# MOD.net
KiCad netlist of a schematic drawn in EAGLE
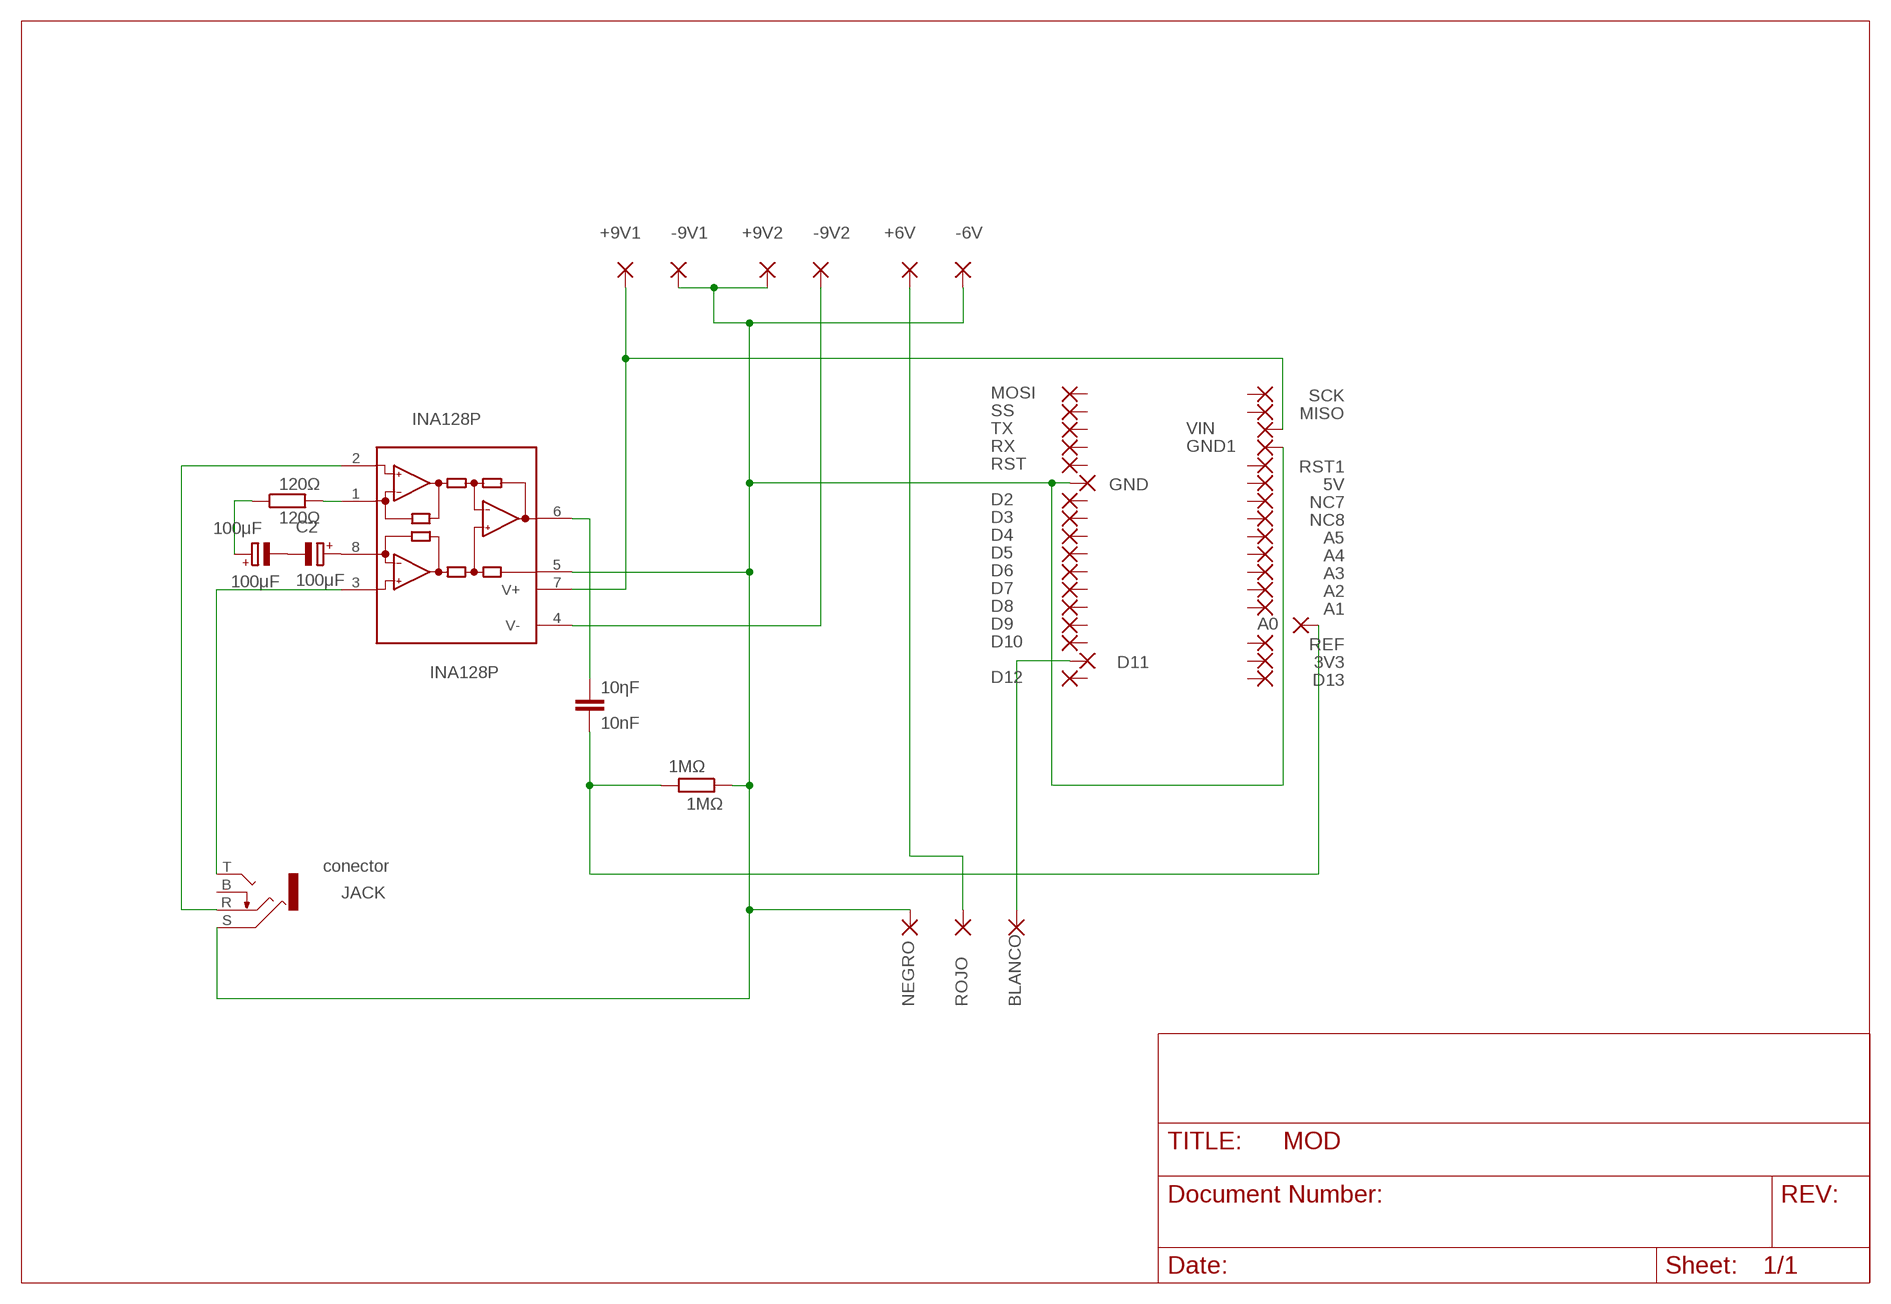
[diagram p0: schematic, sheet 1]

(export (version "E")
  (design (tool "Eeschema 10.0.6"))
  (components
    (comp (ref "+6V")
      (value "2,54/1,1")
      (footprint "eagle-import:2,54_1,1")
      (libsource (lib "eagle-import") (part "2,54/1,1"))
    )
    (comp (ref "+9V1")
      (value "2,54/1,1")
      (footprint "eagle-import:2,54_1,1")
      (libsource (lib "eagle-import") (part "2,54/1,1"))
    )
    (comp (ref "+9V2")
      (value "2,54/1,1")
      (footprint "eagle-import:2,54_1,1")
      (libsource (lib "eagle-import") (part "2,54/1,1"))
    )
    (comp (ref "-6V")
      (value "2,54/1,1")
      (footprint "eagle-import:2,54_1,1")
      (libsource (lib "eagle-import") (part "2,54/1,1"))
    )
    (comp (ref "-9V1")
      (value "2,54/1,1")
      (footprint "eagle-import:2,54_1,1")
      (libsource (lib "eagle-import") (part "2,54/1,1"))
    )
    (comp (ref "-9V2")
      (value "2,54/1,1")
      (footprint "eagle-import:2,54_1,1")
      (libsource (lib "eagle-import") (part "2,54/1,1"))
    )
    (comp (ref "1MΩ")
      (value "1MΩ")
      (footprint "eagle-import:0207_15")
      (libsource (lib "eagle-import") (part "R-EU_0207/15"))
    )
    (comp (ref "3V3")
      (value "1,6/0,9")
      (footprint "eagle-import:1,6_0,9")
      (libsource (lib "eagle-import") (part "1,6/0,9"))
    )
    (comp (ref "5V")
      (value "1,6/0,9")
      (footprint "eagle-import:1,6_0,9")
      (libsource (lib "eagle-import") (part "1,6/0,9"))
    )
    (comp (ref "10ηF")
      (value "10nF")
      (footprint "eagle-import:C050-030X075")
      (libsource (lib "eagle-import") (part "C-EU050-030X075"))
    )
    (comp (ref "100μF")
      (value "100μF")
      (footprint "eagle-import:B45181B")
      (libsource (lib "eagle-import") (part "CPOL-EUB45181B"))
    )
    (comp (ref "120Ω")
      (value "120Ω")
      (footprint "eagle-import:0207_15")
      (libsource (lib "eagle-import") (part "R-EU_0207/15"))
    )
    (comp (ref "A0")
      (value "1,6/0,9")
      (footprint "eagle-import:1,6_0,9")
      (libsource (lib "eagle-import") (part "1,6/0,9"))
    )
    (comp (ref "A1")
      (value "1,6/0,9")
      (footprint "eagle-import:1,6_0,9")
      (libsource (lib "eagle-import") (part "1,6/0,9"))
    )
    (comp (ref "A2")
      (value "1,6/0,9")
      (footprint "eagle-import:1,6_0,9")
      (libsource (lib "eagle-import") (part "1,6/0,9"))
    )
    (comp (ref "A3")
      (value "1,6/0,9")
      (footprint "eagle-import:1,6_0,9")
      (libsource (lib "eagle-import") (part "1,6/0,9"))
    )
    (comp (ref "A4")
      (value "1,6/0,9")
      (footprint "eagle-import:1,6_0,9")
      (libsource (lib "eagle-import") (part "1,6/0,9"))
    )
    (comp (ref "A5")
      (value "1,6/0,9")
      (footprint "eagle-import:1,6_0,9")
      (libsource (lib "eagle-import") (part "1,6/0,9"))
    )
    (comp (ref "BLANCO")
      (value "1,6/0,9")
      (footprint "eagle-import:1,6_0,9")
      (libsource (lib "eagle-import") (part "1,6/0,9"))
    )
    (comp (ref "C2")
      (value "100μF")
      (footprint "eagle-import:B45181B")
      (libsource (lib "eagle-import") (part "CPOL-EUB45181B"))
    )
    (comp (ref "D2")
      (value "1,6/0,9")
      (footprint "eagle-import:1,6_0,9")
      (libsource (lib "eagle-import") (part "1,6/0,9"))
    )
    (comp (ref "D3")
      (value "1,6/0,9")
      (footprint "eagle-import:1,6_0,9")
      (libsource (lib "eagle-import") (part "1,6/0,9"))
    )
    (comp (ref "D4")
      (value "1,6/0,9")
      (footprint "eagle-import:1,6_0,9")
      (libsource (lib "eagle-import") (part "1,6/0,9"))
    )
    (comp (ref "D5")
      (value "1,6/0,9")
      (footprint "eagle-import:1,6_0,9")
      (libsource (lib "eagle-import") (part "1,6/0,9"))
    )
    (comp (ref "D6")
      (value "1,6/0,9")
      (footprint "eagle-import:1,6_0,9")
      (libsource (lib "eagle-import") (part "1,6/0,9"))
    )
    (comp (ref "D7")
      (value "1,6/0,9")
      (footprint "eagle-import:1,6_0,9")
      (libsource (lib "eagle-import") (part "1,6/0,9"))
    )
    (comp (ref "D8")
      (value "1,6/0,9")
      (footprint "eagle-import:1,6_0,9")
      (libsource (lib "eagle-import") (part "1,6/0,9"))
    )
    (comp (ref "D9")
      (value "1,6/0,9")
      (footprint "eagle-import:1,6_0,9")
      (libsource (lib "eagle-import") (part "1,6/0,9"))
    )
    (comp (ref "D10")
      (value "1,6/0,9")
      (footprint "eagle-import:1,6_0,9")
      (libsource (lib "eagle-import") (part "1,6/0,9"))
    )
    (comp (ref "D11")
      (value "1,6/0,9")
      (footprint "eagle-import:1,6_0,9")
      (libsource (lib "eagle-import") (part "1,6/0,9"))
    )
    (comp (ref "D12")
      (value "1,6/0,9")
      (footprint "eagle-import:1,6_0,9")
      (libsource (lib "eagle-import") (part "1,6/0,9"))
    )
    (comp (ref "D13")
      (value "1,6/0,9")
      (footprint "eagle-import:1,6_0,9")
      (libsource (lib "eagle-import") (part "1,6/0,9"))
    )
    (comp (ref "GND")
      (value "1,6/0,9")
      (footprint "eagle-import:1,6_0,9")
      (libsource (lib "eagle-import") (part "1,6/0,9"))
    )
    (comp (ref "GND1")
      (value "1,6/0,9")
      (footprint "eagle-import:1,6_0,9")
      (libsource (lib "eagle-import") (part "1,6/0,9"))
    )
    (comp (ref "INA128P")
      (value "INA128P")
      (footprint "eagle-import:DIL08")
      (fields (field (name "MF") "TEXAS INSTRUMENTS"))
      (libsource (lib "eagle-import") (part "INA128P"))
    )
    (comp (ref "JACK")
      (value "conector")
      (footprint "eagle-import:KLBR4")
      (fields (field (name "MPN") "KLBR 4"))
      (libsource (lib "eagle-import") (part "KLBR4"))
    )
    (comp (ref "MISO")
      (value "1,6/0,9")
      (footprint "eagle-import:1,6_0,9")
      (libsource (lib "eagle-import") (part "1,6/0,9"))
    )
    (comp (ref "MOSI")
      (value "1,6/0,9")
      (footprint "eagle-import:1,6_0,9")
      (libsource (lib "eagle-import") (part "1,6/0,9"))
    )
    (comp (ref "NC7")
      (value "1,6/0,9")
      (footprint "eagle-import:1,6_0,9")
      (libsource (lib "eagle-import") (part "1,6/0,9"))
    )
    (comp (ref "NC8")
      (value "1,6/0,9")
      (footprint "eagle-import:1,6_0,9")
      (libsource (lib "eagle-import") (part "1,6/0,9"))
    )
    (comp (ref "NEGRO")
      (value "1,6/0,9")
      (footprint "eagle-import:1,6_0,9")
      (libsource (lib "eagle-import") (part "1,6/0,9"))
    )
    (comp (ref "REF")
      (value "1,6/0,9")
      (footprint "eagle-import:1,6_0,9")
      (libsource (lib "eagle-import") (part "1,6/0,9"))
    )
    (comp (ref "ROJO")
      (value "1,6/0,9")
      (footprint "eagle-import:1,6_0,9")
      (libsource (lib "eagle-import") (part "1,6/0,9"))
    )
    (comp (ref "RST")
      (value "1,6/0,9")
      (footprint "eagle-import:1,6_0,9")
      (libsource (lib "eagle-import") (part "1,6/0,9"))
    )
    (comp (ref "RST1")
      (value "1,6/0,9")
      (footprint "eagle-import:1,6_0,9")
      (libsource (lib "eagle-import") (part "1,6/0,9"))
    )
    (comp (ref "RX")
      (value "1,6/0,9")
      (footprint "eagle-import:1,6_0,9")
      (libsource (lib "eagle-import") (part "1,6/0,9"))
    )
    (comp (ref "SCK")
      (value "1,6/0,9")
      (footprint "eagle-import:1,6_0,9")
      (libsource (lib "eagle-import") (part "1,6/0,9"))
    )
    (comp (ref "SS")
      (value "1,6/0,9")
      (footprint "eagle-import:1,6_0,9")
      (libsource (lib "eagle-import") (part "1,6/0,9"))
    )
    (comp (ref "TX")
      (value "1,6/0,9")
      (footprint "eagle-import:1,6_0,9")
      (libsource (lib "eagle-import") (part "1,6/0,9"))
    )
    (comp (ref "VIN")
      (value "1,6/0,9")
      (footprint "eagle-import:1,6_0,9")
      (libsource (lib "eagle-import") (part "1,6/0,9"))
    )
  )
  (nets
    (net (code "1") (name "Net-(+6V-P)") (class "Default")
      (node (ref "+6V") (pin "1") (pinfunction "P_1") (pintype "passive"))
      (node (ref "ROJO") (pin "1") (pinfunction "P_1") (pintype "passive"))
    )
    (net (code "2") (name "Net-(+9V1-P)") (class "Default")
      (node (ref "+9V1") (pin "1") (pinfunction "P_1") (pintype "passive"))
      (node (ref "INA128P") (pin "7") (pinfunction "V+_7") (pintype "power_in"))
      (node (ref "VIN") (pin "1") (pinfunction "P_1") (pintype "passive"))
    )
    (net (code "3") (name "Net-(+9V2-P)") (class "Default")
      (node (ref "+9V2") (pin "1") (pinfunction "P_1") (pintype "passive"))
      (node (ref "-6V") (pin "1") (pinfunction "P_1") (pintype "passive"))
      (node (ref "-9V1") (pin "1") (pinfunction "P_1") (pintype "passive"))
      (node (ref "1MΩ") (pin "1") (pinfunction "1_1") (pintype "passive"))
      (node (ref "GND") (pin "1") (pinfunction "P_1") (pintype "passive"))
      (node (ref "GND1") (pin "1") (pinfunction "P_1") (pintype "passive"))
      (node (ref "INA128P") (pin "5") (pinfunction "REF_5") (pintype "passive"))
      (node (ref "JACK") (pin "S") (pinfunction "S_S") (pintype "passive"))
      (node (ref "NEGRO") (pin "1") (pinfunction "P_1") (pintype "passive"))
    )
    (net (code "4") (name "Net-(-9V2-P)") (class "Default")
      (node (ref "-9V2") (pin "1") (pinfunction "P_1") (pintype "passive"))
      (node (ref "INA128P") (pin "4") (pinfunction "V-_4") (pintype "power_in"))
    )
    (net (code "5") (name "Net-(100μF-Pad+)") (class "Default")
      (node (ref "100μF") (pin "+") (pinfunction "+_+") (pintype "passive"))
      (node (ref "120Ω") (pin "1") (pinfunction "1_1") (pintype "passive"))
    )
    (net (code "6") (name "Net-(100μF-Pad-)") (class "Default")
      (node (ref "100μF") (pin "-") (pinfunction "-_-") (pintype "passive"))
      (node (ref "C2") (pin "-") (pinfunction "-_-") (pintype "passive"))
    )
    (net (code "7") (name "Net-(120Ω-Pad2)") (class "Default")
      (node (ref "120Ω") (pin "2") (pinfunction "2_2") (pintype "passive"))
      (node (ref "INA128P") (pin "1") (pinfunction "RG_1") (pintype "passive"))
    )
    (net (code "8") (name "Net-(A0-P)") (class "Default")
      (node (ref "10ηF") (pin "2") (pinfunction "2_2") (pintype "passive"))
      (node (ref "1MΩ") (pin "2") (pinfunction "2_2") (pintype "passive"))
      (node (ref "A0") (pin "1") (pinfunction "P_1") (pintype "passive"))
    )
    (net (code "9") (name "Net-(BLANCO-P)") (class "Default")
      (node (ref "BLANCO") (pin "1") (pinfunction "P_1") (pintype "passive"))
      (node (ref "D11") (pin "1") (pinfunction "P_1") (pintype "passive"))
    )
    (net (code "10") (name "Net-(C2-Pad+)") (class "Default")
      (node (ref "C2") (pin "+") (pinfunction "+_+") (pintype "passive"))
      (node (ref "INA128P") (pin "8") (pinfunction "RG_8") (pintype "passive"))
    )
    (net (code "11") (name "Net-(INA128P-+IN)") (class "Default")
      (node (ref "INA128P") (pin "3") (pinfunction "+IN_3") (pintype "input"))
      (node (ref "JACK") (pin "T") (pinfunction "T_T") (pintype "passive"))
    )
    (net (code "12") (name "Net-(INA128P--IN)") (class "Default")
      (node (ref "INA128P") (pin "2") (pinfunction "-IN_2") (pintype "input"))
      (node (ref "JACK") (pin "R") (pinfunction "R_R") (pintype "passive"))
    )
    (net (code "13") (name "Net-(INA128P-OUT)") (class "Default")
      (node (ref "10ηF") (pin "1") (pinfunction "1_1") (pintype "passive"))
      (node (ref "INA128P") (pin "6") (pinfunction "OUT_6") (pintype "output"))
    )
    (net (code "14") (name "unconnected-(3V3-P-Pad1)") (class "Default")
      (node (ref "3V3") (pin "1") (pinfunction "P_1") (pintype "passive"))
    )
    (net (code "15") (name "unconnected-(5V-P-Pad1)") (class "Default")
      (node (ref "5V") (pin "1") (pinfunction "P_1") (pintype "passive"))
    )
    (net (code "16") (name "unconnected-(A1-P-Pad1)") (class "Default")
      (node (ref "A1") (pin "1") (pinfunction "P_1") (pintype "passive"))
    )
    (net (code "17") (name "unconnected-(A2-P-Pad1)") (class "Default")
      (node (ref "A2") (pin "1") (pinfunction "P_1") (pintype "passive"))
    )
    (net (code "18") (name "unconnected-(A3-P-Pad1)") (class "Default")
      (node (ref "A3") (pin "1") (pinfunction "P_1") (pintype "passive"))
    )
    (net (code "19") (name "unconnected-(A4-P-Pad1)") (class "Default")
      (node (ref "A4") (pin "1") (pinfunction "P_1") (pintype "passive"))
    )
    (net (code "20") (name "unconnected-(A5-P-Pad1)") (class "Default")
      (node (ref "A5") (pin "1") (pinfunction "P_1") (pintype "passive"))
    )
    (net (code "21") (name "unconnected-(D2-P-Pad1)") (class "Default")
      (node (ref "D2") (pin "1") (pinfunction "P_1") (pintype "passive"))
    )
    (net (code "22") (name "unconnected-(D3-P-Pad1)") (class "Default")
      (node (ref "D3") (pin "1") (pinfunction "P_1") (pintype "passive"))
    )
    (net (code "23") (name "unconnected-(D4-P-Pad1)") (class "Default")
      (node (ref "D4") (pin "1") (pinfunction "P_1") (pintype "passive"))
    )
    (net (code "24") (name "unconnected-(D5-P-Pad1)") (class "Default")
      (node (ref "D5") (pin "1") (pinfunction "P_1") (pintype "passive"))
    )
    (net (code "25") (name "unconnected-(D6-P-Pad1)") (class "Default")
      (node (ref "D6") (pin "1") (pinfunction "P_1") (pintype "passive"))
    )
    (net (code "26") (name "unconnected-(D7-P-Pad1)") (class "Default")
      (node (ref "D7") (pin "1") (pinfunction "P_1") (pintype "passive"))
    )
    (net (code "27") (name "unconnected-(D8-P-Pad1)") (class "Default")
      (node (ref "D8") (pin "1") (pinfunction "P_1") (pintype "passive"))
    )
    (net (code "28") (name "unconnected-(D9-P-Pad1)") (class "Default")
      (node (ref "D9") (pin "1") (pinfunction "P_1") (pintype "passive"))
    )
    (net (code "29") (name "unconnected-(D10-P-Pad1)") (class "Default")
      (node (ref "D10") (pin "1") (pinfunction "P_1") (pintype "passive"))
    )
    (net (code "30") (name "unconnected-(D12-P-Pad1)") (class "Default")
      (node (ref "D12") (pin "1") (pinfunction "P_1") (pintype "passive"))
    )
    (net (code "31") (name "unconnected-(D13-P-Pad1)") (class "Default")
      (node (ref "D13") (pin "1") (pinfunction "P_1") (pintype "passive"))
    )
    (net (code "32") (name "unconnected-(JACK-PadB)") (class "Default")
      (node (ref "JACK") (pin "B") (pinfunction "B_B") (pintype "passive"))
    )
    (net (code "33") (name "unconnected-(MISO-P-Pad1)") (class "Default")
      (node (ref "MISO") (pin "1") (pinfunction "P_1") (pintype "passive"))
    )
    (net (code "34") (name "unconnected-(MOSI-P-Pad1)") (class "Default")
      (node (ref "MOSI") (pin "1") (pinfunction "P_1") (pintype "passive"))
    )
    (net (code "35") (name "unconnected-(NC7-P-Pad1)") (class "Default")
      (node (ref "NC7") (pin "1") (pinfunction "P_1") (pintype "passive"))
    )
    (net (code "36") (name "unconnected-(NC8-P-Pad1)") (class "Default")
      (node (ref "NC8") (pin "1") (pinfunction "P_1") (pintype "passive"))
    )
    (net (code "37") (name "unconnected-(REF-P-Pad1)") (class "Default")
      (node (ref "REF") (pin "1") (pinfunction "P_1") (pintype "passive"))
    )
    (net (code "38") (name "unconnected-(RST-P-Pad1)") (class "Default")
      (node (ref "RST") (pin "1") (pinfunction "P_1") (pintype "passive"))
    )
    (net (code "39") (name "unconnected-(RST1-P-Pad1)") (class "Default")
      (node (ref "RST1") (pin "1") (pinfunction "P_1") (pintype "passive"))
    )
    (net (code "40") (name "unconnected-(RX-P-Pad1)") (class "Default")
      (node (ref "RX") (pin "1") (pinfunction "P_1") (pintype "passive"))
    )
    (net (code "41") (name "unconnected-(SCK-P-Pad1)") (class "Default")
      (node (ref "SCK") (pin "1") (pinfunction "P_1") (pintype "passive"))
    )
    (net (code "42") (name "unconnected-(SS-P-Pad1)") (class "Default")
      (node (ref "SS") (pin "1") (pinfunction "P_1") (pintype "passive"))
    )
    (net (code "43") (name "unconnected-(TX-P-Pad1)") (class "Default")
      (node (ref "TX") (pin "1") (pinfunction "P_1") (pintype "passive"))
    )
  )
)
